# CAN.net
KiCad netlist of a schematic drawn in Altium Designer
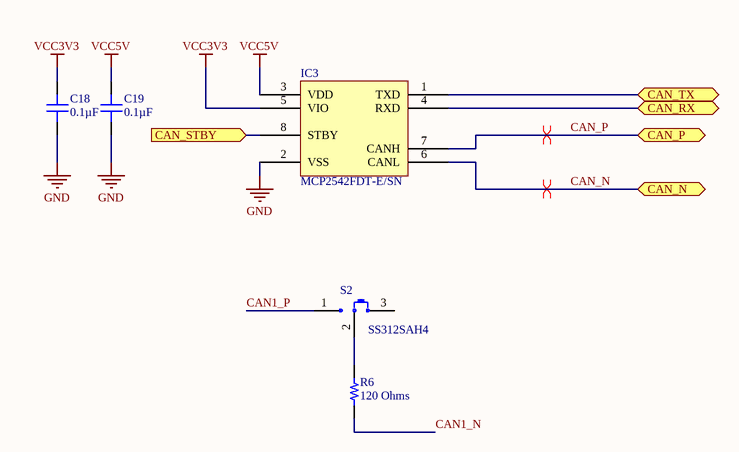
[diagram p0: CAN.SchDoc]

(export (version "E")
  (design (tool "Eeschema 10.0.6"))
  (components
    (comp (ref "C18")
      (value "0.1µF")
      (footprint "CAP 0201_0603")
      (description "CAP CER 0.1UF 16V X5R 0201")
      (fields (field (name "PART NUMBER") "EMK063BJ104KP-F") (field (name "MANUFACTURER") "Taiyo Yuden"))
      (libsource (lib "Celestial") (part "Capacitor"))
    )
    (comp (ref "C19")
      (value "0.1µF")
      (footprint "CAP 0201_0603")
      (description "CAP CER 0.1UF 16V X5R 0201")
      (fields (field (name "PART NUMBER") "EMK063BJ104KP-F") (field (name "MANUFACTURER") "Taiyo Yuden"))
      (libsource (lib "Celestial") (part "Capacitor"))
    )
    (comp (ref "IC3")
      (value "MCP2542FDT-E/SN")
      (footprint "MICROCHIP SOIC-8 150MIL WIDE")
      (description "IC TRANSCEIVER 1/1 8SOIC")
      (fields (field (name "MANUFACTURER") "Microchip Technology"))
      (libsource (lib "Celestial") (part "MICROCHIP MCP2542FD"))
    )
    (comp (ref "R6")
      (value "120 Ohms")
      (footprint "RES 0402_1005")
      (description "RES SMD 120 OHM 5% 1/16W 0402")
      (fields (field (name "PART NUMBER") "RC0402JR-07120RL") (field (name "MANUFACTURER") "Yageo"))
      (libsource (lib "CAL") (part "Resistor"))
    )
    (comp (ref "S2")
      (value "SS312SAH4")
      (footprint "NKK SS312SAH4")
      (description "SWITCH SLIDE SPDT 0.4VA 28V")
      (fields (field (name "MANUFACTURER") "NKK Switches"))
      (libsource (lib "CAL") (part "NKK SS312"))
    )
  )
  (nets
    (net (code "1") (name "/CAN1_N") (class "Default")
      (node (ref "R6") (pin "1") (pinfunction "1_1") (pintype "passive"))
    )
    (net (code "2") (name "/CAN1_P") (class "Default")
      (node (ref "S2") (pin "1") (pinfunction "1_1") (pintype "passive"))
    )
    (net (code "3") (name "/CAN_N") (class "Default")
      (node (ref "IC3") (pin "6") (pinfunction "CANL_6") (pintype "passive"))
    )
    (net (code "4") (name "/CAN_P") (class "Default")
      (node (ref "IC3") (pin "7") (pinfunction "CANH_7") (pintype "passive"))
    )
    (net (code "5") (name "/CAN_RX") (class "Default")
      (node (ref "IC3") (pin "4") (pinfunction "RXD_4") (pintype "passive"))
    )
    (net (code "6") (name "/CAN_STBY") (class "Default")
      (node (ref "IC3") (pin "8") (pinfunction "STBY_8") (pintype "passive"))
    )
    (net (code "7") (name "/CAN_TX") (class "Default")
      (node (ref "IC3") (pin "1") (pinfunction "TXD_1") (pintype "passive"))
    )
    (net (code "8") (name "GND") (class "Default")
      (node (ref "C18") (pin "1") (pinfunction "1_1") (pintype "passive"))
      (node (ref "C19") (pin "1") (pinfunction "1_1") (pintype "passive"))
      (node (ref "IC3") (pin "2") (pinfunction "VSS_2") (pintype "passive"))
    )
    (net (code "9") (name "Net-(S2-COM)") (class "Default")
      (node (ref "R6") (pin "2") (pinfunction "2_2") (pintype "passive"))
      (node (ref "S2") (pin "2") (pinfunction "COM_2") (pintype "passive"))
    )
    (net (code "10") (name "VCC3V3") (class "Default")
      (node (ref "C18") (pin "2") (pinfunction "2_2") (pintype "passive"))
      (node (ref "IC3") (pin "5") (pinfunction "VIO_5") (pintype "passive"))
    )
    (net (code "11") (name "VCC5V") (class "Default")
      (node (ref "C19") (pin "2") (pinfunction "2_2") (pintype "passive"))
      (node (ref "IC3") (pin "3") (pinfunction "VDD_3") (pintype "passive"))
    )
    (net (code "12") (name "unconnected-(S2-Pad3)") (class "Default")
      (node (ref "S2") (pin "3") (pinfunction "3_3") (pintype "passive"))
    )
  )
)
